# panel_board_CHM.net
KiCad netlist of a schematic drawn in Altium Designer
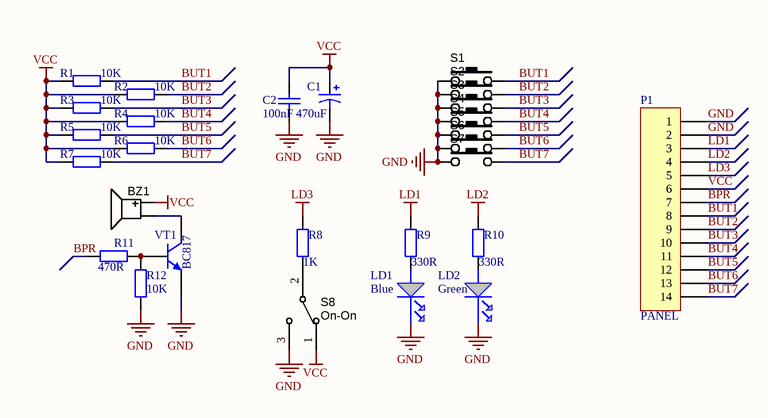
[diagram p0: panel_board_CHM.SchDoc]

(export (version "E")
  (design (tool "Eeschema 10.0.6"))
  (components
    (comp (ref "BZ1")
      (value "Alternate part: 3100-932")
      (footprint "BUZZER_12.0X8.5MM")
      (description "Speaker, Magnetic Transducer")
      (libsource (lib "PBL - Electromechanical") (part "BZ_12x8.5x6.5_2kHz"))
    )
    (comp (ref "C1")
      (value "470uF")
      (footprint "CAPAE200P550X1200_FLAT1")
      (description "Polarized Capacitor (Radial)")
      (fields (field (name "Comment") "Cap Pol1") (field (name "PUBLISHER") "Altium Limited"))
      (libsource (lib "Miscellaneous Devices") (part "Cap Pol1"))
    )
    (comp (ref "C2")
      (value "100nF")
      (footprint "CAPC2012X135N")
      (description "Ceramic Chip Capacitor - Standard")
      (fields (field (name "Comment") "C0805") (field (name "PUBLISHER") "Altium Limited"))
      (libsource (lib "KEMET Chip Capacitor") (part "C0805"))
    )
    (comp (ref "LD1")
      (value "Blue")
      (footprint "LED-0603-BLUE")
      (description "APT1608QBC/D")
      (fields (field (name "Comment") "PWR_L"))
      (libsource (lib "discret") (part "LED"))
    )
    (comp (ref "LD2")
      (value "Green")
      (footprint "LED-0603-GREEN")
      (description "APT1608QBC/D")
      (fields (field (name "Comment") "PWR_H"))
      (libsource (lib "discret") (part "LED"))
    )
    (comp (ref "P1")
      (value "PANEL")
      (footprint "14P_PCB_HEADER_BRD_MNT")
      (description "Header, 14-Pin")
      (fields (field (name "PUBLISHER") "Altium Limited"))
      (libsource (lib "Miscellaneous Connectors") (part "Header 14"))
    )
    (comp (ref "R1")
      (value "10K")
      (footprint "RESC2012X70N")
      (description "Resistor")
      (fields (field (name "Comment") "Res2") (field (name "PUBLISHER") "Altium Limited"))
      (libsource (lib "Miscellaneous Devices") (part "Res2"))
    )
    (comp (ref "R2")
      (value "10K")
      (footprint "RESC2012X70N")
      (description "Resistor")
      (fields (field (name "Comment") "Res2") (field (name "PUBLISHER") "Altium Limited"))
      (libsource (lib "Miscellaneous Devices") (part "Res2"))
    )
    (comp (ref "R3")
      (value "10K")
      (footprint "RESC2012X70N")
      (description "Resistor")
      (fields (field (name "Comment") "Res2") (field (name "PUBLISHER") "Altium Limited"))
      (libsource (lib "Miscellaneous Devices") (part "Res2"))
    )
    (comp (ref "R4")
      (value "10K")
      (footprint "RESC2012X70N")
      (description "Resistor")
      (fields (field (name "Comment") "Res2") (field (name "PUBLISHER") "Altium Limited"))
      (libsource (lib "Miscellaneous Devices") (part "Res2"))
    )
    (comp (ref "R5")
      (value "10K")
      (footprint "RESC2012X70N")
      (description "Resistor")
      (fields (field (name "Comment") "Res2") (field (name "PUBLISHER") "Altium Limited"))
      (libsource (lib "Miscellaneous Devices") (part "Res2"))
    )
    (comp (ref "R6")
      (value "10K")
      (footprint "RESC2012X70N")
      (description "Resistor")
      (fields (field (name "Comment") "Res2") (field (name "PUBLISHER") "Altium Limited"))
      (libsource (lib "Miscellaneous Devices") (part "Res2"))
    )
    (comp (ref "R7")
      (value "10K")
      (footprint "RESC2012X70N")
      (description "Resistor")
      (fields (field (name "Comment") "Res2") (field (name "PUBLISHER") "Altium Limited"))
      (libsource (lib "Miscellaneous Devices") (part "Res2"))
    )
    (comp (ref "R8")
      (value "1K")
      (footprint "RESC2012X70N")
      (description "Resistor")
      (fields (field (name "Comment") "Res2") (field (name "PUBLISHER") "Altium Limited"))
      (libsource (lib "") (part "Res2_1"))
    )
    (comp (ref "R9")
      (value "330R")
      (footprint "RESC2012X70N")
      (description "Resistor")
      (fields (field (name "Comment") "Res2") (field (name "PUBLISHER") "Altium Limited"))
      (libsource (lib "") (part "Res2_1"))
    )
    (comp (ref "R10")
      (value "330R")
      (footprint "RESC2012X70N")
      (description "Resistor")
      (fields (field (name "Comment") "Res2") (field (name "PUBLISHER") "Altium Limited"))
      (libsource (lib "") (part "Res2_1"))
    )
    (comp (ref "R11")
      (value "470R")
      (footprint "RESC2012X70N")
      (description "Resistor")
      (fields (field (name "Comment") "Res2") (field (name "PUBLISHER") "Altium Limited"))
      (libsource (lib "Miscellaneous Devices") (part "Res2"))
    )
    (comp (ref "R12")
      (value "10K")
      (footprint "RESC2012X70N")
      (description "Resistor")
      (fields (field (name "Comment") "Res2") (field (name "PUBLISHER") "Altium Limited"))
      (libsource (lib "") (part "Res2_1"))
    )
    (comp (ref "S1")
      (value "SW_THT_PB_7.0mm")
      (footprint "TACT-SWITCH-TS1170")
      (description "Switch, tact, 7.0mm stem")
      (libsource (lib "PBL - Switches") (part "SW_THT_PB_7.0mm"))
    )
    (comp (ref "S2")
      (value "SW_THT_PB_7.0mm")
      (footprint "TACT-SWITCH-TS1170")
      (description "Switch, tact, 7.0mm stem")
      (libsource (lib "PBL - Switches") (part "SW_THT_PB_7.0mm"))
    )
    (comp (ref "S3")
      (value "SW_THT_PB_7.0mm")
      (footprint "TACT-SWITCH-TS1170")
      (description "Switch, tact, 7.0mm stem")
      (libsource (lib "PBL - Switches") (part "SW_THT_PB_7.0mm"))
    )
    (comp (ref "S4")
      (value "SW_THT_PB_7.0mm")
      (footprint "TACT-SWITCH-TS1170")
      (description "Switch, tact, 7.0mm stem")
      (libsource (lib "PBL - Switches") (part "SW_THT_PB_7.0mm"))
    )
    (comp (ref "S5")
      (value "SW_THT_PB_7.0mm")
      (footprint "TACT-SWITCH-TS1170")
      (description "Switch, tact, 7.0mm stem")
      (libsource (lib "PBL - Switches") (part "SW_THT_PB_7.0mm"))
    )
    (comp (ref "S6")
      (value "SW_THT_PB_7.0mm")
      (footprint "TACT-SWITCH-TS1170")
      (description "Switch, tact, 7.0mm stem")
      (libsource (lib "PBL - Switches") (part "SW_THT_PB_7.0mm"))
    )
    (comp (ref "S7")
      (value "SW_THT_PB_7.0mm")
      (footprint "TACT-SWITCH-TS1170")
      (description "Switch, tact, 7.0mm stem")
      (libsource (lib "PBL - Switches") (part "SW_THT_PB_7.0mm"))
    )
    (comp (ref "S8")
      (value "ON-ON")
      (footprint "SWITCH_SPDT_SLIDER")
      (description "Switch THD vertical toggle SPDT")
      (fields (field (name "SWITCH FUNCTION") "On-On"))
      (libsource (lib "PBL - Switches") (part "SW_THD_SPDT_On-On"))
    )
    (comp (ref "VT1")
      (value "BC817")
      (footprint "SOT23-3")
      (description "NPN Bipolar Transistor")
      (fields (field (name "PUBLISHER") "Altium Limited"))
      (libsource (lib "Miscellaneous Devices") (part "QNPN"))
    )
  )
  (nets
    (net (code "1") (name "/BPR") (class "Default")
      (node (ref "P1") (pin "7") (pinfunction "7_7") (pintype "passive"))
      (node (ref "R11") (pin "1") (pinfunction "1_1") (pintype "passive"))
    )
    (net (code "2") (name "/BUT1") (class "Default")
      (node (ref "P1") (pin "8") (pinfunction "8_8") (pintype "passive"))
      (node (ref "R1") (pin "2") (pinfunction "2_2") (pintype "passive"))
      (node (ref "S1") (pin "2") (pintype "passive"))
    )
    (net (code "3") (name "/BUT2") (class "Default")
      (node (ref "P1") (pin "9") (pinfunction "9_9") (pintype "passive"))
      (node (ref "R2") (pin "2") (pinfunction "2_2") (pintype "passive"))
      (node (ref "S2") (pin "2") (pintype "passive"))
    )
    (net (code "4") (name "/BUT3") (class "Default")
      (node (ref "P1") (pin "10") (pinfunction "10_10") (pintype "passive"))
      (node (ref "R3") (pin "2") (pinfunction "2_2") (pintype "passive"))
      (node (ref "S3") (pin "2") (pintype "passive"))
    )
    (net (code "5") (name "/BUT4") (class "Default")
      (node (ref "P1") (pin "11") (pinfunction "11_11") (pintype "passive"))
      (node (ref "R4") (pin "2") (pinfunction "2_2") (pintype "passive"))
      (node (ref "S4") (pin "2") (pintype "passive"))
    )
    (net (code "6") (name "/BUT5") (class "Default")
      (node (ref "P1") (pin "12") (pinfunction "12_12") (pintype "passive"))
      (node (ref "R5") (pin "2") (pinfunction "2_2") (pintype "passive"))
      (node (ref "S5") (pin "2") (pintype "passive"))
    )
    (net (code "7") (name "/BUT6") (class "Default")
      (node (ref "P1") (pin "13") (pinfunction "13_13") (pintype "passive"))
      (node (ref "R6") (pin "2") (pinfunction "2_2") (pintype "passive"))
      (node (ref "S6") (pin "2") (pintype "passive"))
    )
    (net (code "8") (name "/BUT7") (class "Default")
      (node (ref "P1") (pin "14") (pinfunction "14_14") (pintype "passive"))
      (node (ref "R7") (pin "2") (pinfunction "2_2") (pintype "passive"))
      (node (ref "S7") (pin "2") (pintype "passive"))
    )
    (net (code "9") (name "GND") (class "Default")
      (node (ref "C1") (pin "2") (pinfunction "2_2") (pintype "passive"))
      (node (ref "C2") (pin "1") (pinfunction "1_1") (pintype "passive"))
      (node (ref "LD1") (pin "K") (pinfunction "CATODE_K") (pintype "passive"))
      (node (ref "LD2") (pin "K") (pinfunction "CATODE_K") (pintype "passive"))
      (node (ref "P1") (pin "1") (pinfunction "1_1") (pintype "passive"))
      (node (ref "P1") (pin "2") (pinfunction "2_2") (pintype "passive"))
      (node (ref "R12") (pin "1") (pinfunction "1_1") (pintype "passive"))
      (node (ref "S1") (pin "1") (pintype "passive"))
      (node (ref "S2") (pin "1") (pintype "passive"))
      (node (ref "S3") (pin "1") (pintype "passive"))
      (node (ref "S4") (pin "1") (pintype "passive"))
      (node (ref "S5") (pin "1") (pintype "passive"))
      (node (ref "S6") (pin "1") (pintype "passive"))
      (node (ref "S7") (pin "1") (pintype "passive"))
      (node (ref "S8") (pin "3") (pinfunction "3_3") (pintype "passive"))
      (node (ref "VT1") (pin "3") (pinfunction "E_3") (pintype "passive"))
    )
    (net (code "10") (name "LD1") (class "Default")
      (node (ref "P1") (pin "3") (pinfunction "3_3") (pintype "passive"))
      (node (ref "R9") (pin "2") (pinfunction "2_2") (pintype "passive"))
    )
    (net (code "11") (name "LD2") (class "Default")
      (node (ref "P1") (pin "4") (pinfunction "4_4") (pintype "passive"))
      (node (ref "R10") (pin "2") (pinfunction "2_2") (pintype "passive"))
    )
    (net (code "12") (name "LD3") (class "Default")
      (node (ref "P1") (pin "5") (pinfunction "5_5") (pintype "passive"))
      (node (ref "R8") (pin "2") (pinfunction "2_2") (pintype "passive"))
    )
    (net (code "13") (name "Net-(BZ1-Negative)") (class "Default")
      (node (ref "BZ1") (pin "2") (pinfunction "Negative_2") (pintype "passive"))
      (node (ref "VT1") (pin "1") (pinfunction "C_1") (pintype "passive"))
    )
    (net (code "14") (name "Net-(LD1-ANODE)") (class "Default")
      (node (ref "LD1") (pin "A") (pinfunction "ANODE_A") (pintype "passive"))
      (node (ref "R9") (pin "1") (pinfunction "1_1") (pintype "passive"))
    )
    (net (code "15") (name "Net-(LD2-ANODE)") (class "Default")
      (node (ref "LD2") (pin "A") (pinfunction "ANODE_A") (pintype "passive"))
      (node (ref "R10") (pin "1") (pinfunction "1_1") (pintype "passive"))
    )
    (net (code "16") (name "Net-(R8-Pad1)") (class "Default")
      (node (ref "R8") (pin "1") (pinfunction "1_1") (pintype "passive"))
      (node (ref "S8") (pin "2") (pinfunction "2_2") (pintype "passive"))
    )
    (net (code "17") (name "Net-(VT1-B)") (class "Default")
      (node (ref "R11") (pin "2") (pinfunction "2_2") (pintype "passive"))
      (node (ref "R12") (pin "2") (pinfunction "2_2") (pintype "passive"))
      (node (ref "VT1") (pin "2") (pinfunction "B_2") (pintype "passive"))
    )
    (net (code "18") (name "VCC") (class "Default")
      (node (ref "BZ1") (pin "1") (pinfunction "Positive_1") (pintype "passive"))
      (node (ref "C1") (pin "1") (pinfunction "1_1") (pintype "passive"))
      (node (ref "C2") (pin "2") (pinfunction "2_2") (pintype "passive"))
      (node (ref "P1") (pin "6") (pinfunction "6_6") (pintype "passive"))
      (node (ref "R1") (pin "1") (pinfunction "1_1") (pintype "passive"))
      (node (ref "R2") (pin "1") (pinfunction "1_1") (pintype "passive"))
      (node (ref "R3") (pin "1") (pinfunction "1_1") (pintype "passive"))
      (node (ref "R4") (pin "1") (pinfunction "1_1") (pintype "passive"))
      (node (ref "R5") (pin "1") (pinfunction "1_1") (pintype "passive"))
      (node (ref "R6") (pin "1") (pinfunction "1_1") (pintype "passive"))
      (node (ref "R7") (pin "1") (pinfunction "1_1") (pintype "passive"))
      (node (ref "S8") (pin "1") (pinfunction "1_1") (pintype "passive"))
    )
  )
)
